# Sheet1.net
KiCad netlist of a schematic drawn in Altium Designer
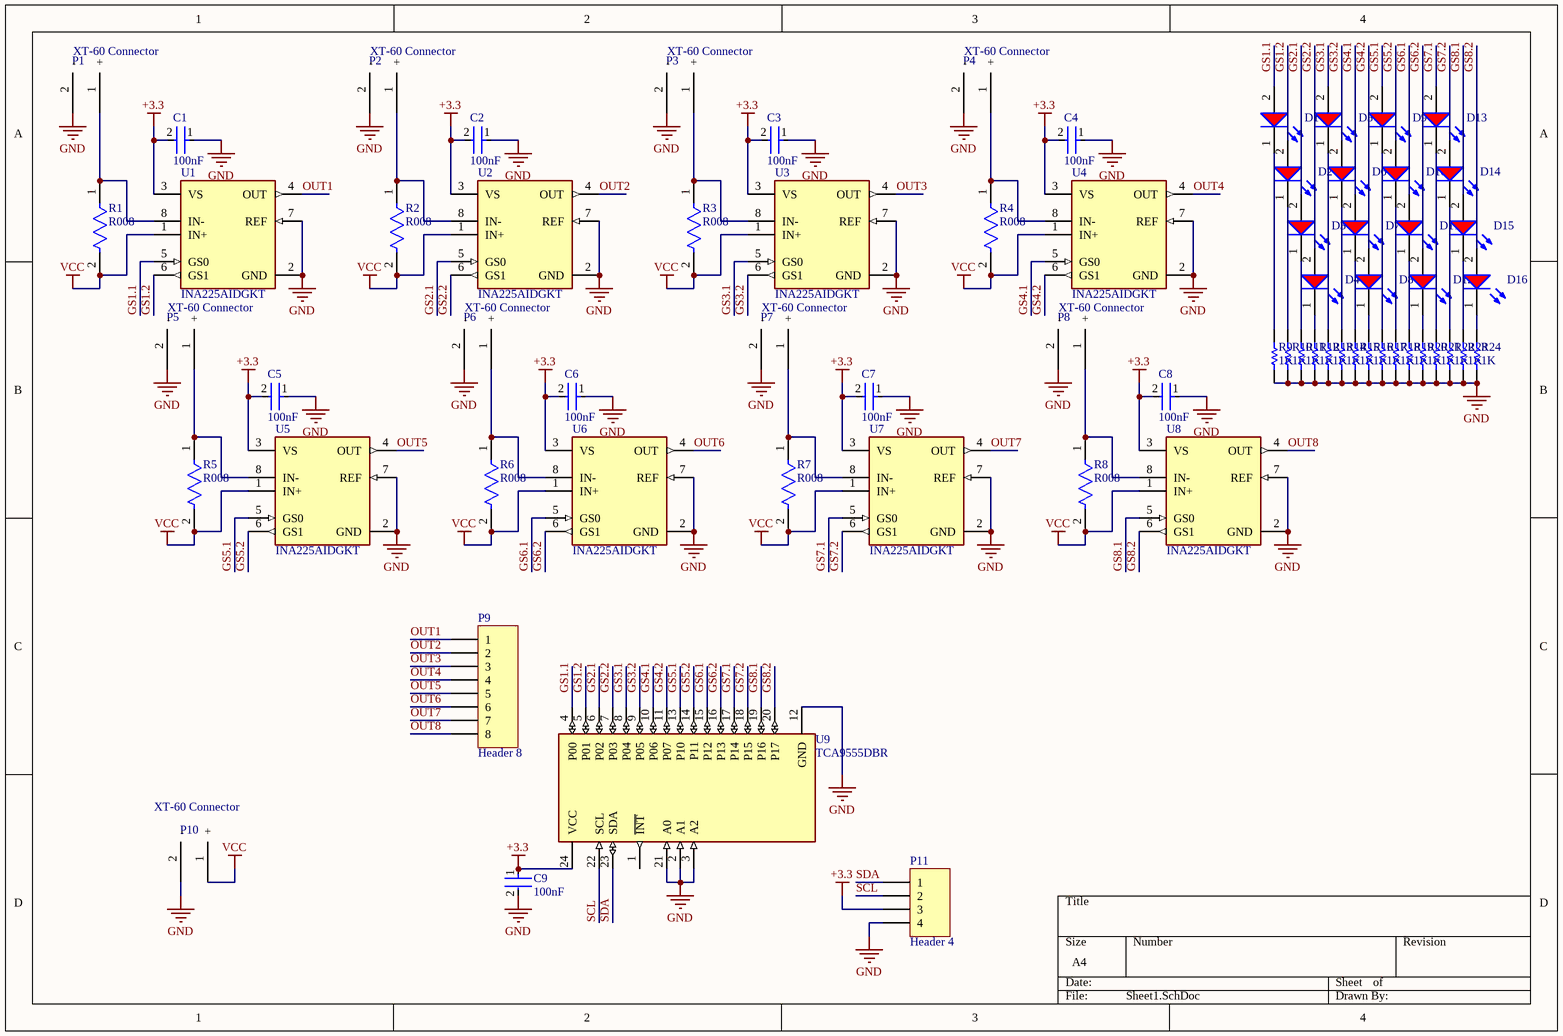
[diagram p0: Sheet1.SchDoc]

(export (version "E")
  (design (tool "Eeschema 10.0.6"))
  (components
    (comp (ref "C1")
      (value "100nF")
      (footprint "FP-0805-L_2_01_0_2-W_1_25-IPC_B")
      (description "General Purpose Ceramic Capacitor, 0805, 100nF, 10%, X7R, 15%, 100V")
      (fields (field (name "VOLTAGE") "100V") (field (name "TOLERANCE") "10%"))
      (libsource (lib "Altium Content Vault") (part "b4654b650e69147ec39a6b967a45e02"))
    )
    (comp (ref "C2")
      (value "100nF")
      (footprint "FP-0805-L_2_01_0_2-W_1_25-IPC_B")
      (description "General Purpose Ceramic Capacitor, 0805, 100nF, 10%, X7R, 15%, 100V")
      (fields (field (name "VOLTAGE") "100V") (field (name "TOLERANCE") "10%"))
      (libsource (lib "Altium Content Vault") (part "b4654b650e69147ec39a6b967a45e02"))
    )
    (comp (ref "C3")
      (value "100nF")
      (footprint "FP-0805-L_2_01_0_2-W_1_25-IPC_B")
      (description "General Purpose Ceramic Capacitor, 0805, 100nF, 10%, X7R, 15%, 100V")
      (fields (field (name "VOLTAGE") "100V") (field (name "TOLERANCE") "10%"))
      (libsource (lib "Altium Content Vault") (part "b4654b650e69147ec39a6b967a45e02"))
    )
    (comp (ref "C4")
      (value "100nF")
      (footprint "FP-0805-L_2_01_0_2-W_1_25-IPC_B")
      (description "General Purpose Ceramic Capacitor, 0805, 100nF, 10%, X7R, 15%, 100V")
      (fields (field (name "VOLTAGE") "100V") (field (name "TOLERANCE") "10%"))
      (libsource (lib "Altium Content Vault") (part "b4654b650e69147ec39a6b967a45e02"))
    )
    (comp (ref "C5")
      (value "100nF")
      (footprint "FP-0805-L_2_01_0_2-W_1_25-IPC_B")
      (description "General Purpose Ceramic Capacitor, 0805, 100nF, 10%, X7R, 15%, 100V")
      (fields (field (name "VOLTAGE") "100V") (field (name "TOLERANCE") "10%"))
      (libsource (lib "Altium Content Vault") (part "b4654b650e69147ec39a6b967a45e02"))
    )
    (comp (ref "C6")
      (value "100nF")
      (footprint "FP-0805-L_2_01_0_2-W_1_25-IPC_B")
      (description "General Purpose Ceramic Capacitor, 0805, 100nF, 10%, X7R, 15%, 100V")
      (fields (field (name "VOLTAGE") "100V") (field (name "TOLERANCE") "10%"))
      (libsource (lib "Altium Content Vault") (part "b4654b650e69147ec39a6b967a45e02"))
    )
    (comp (ref "C7")
      (value "100nF")
      (footprint "FP-0805-L_2_01_0_2-W_1_25-IPC_B")
      (description "General Purpose Ceramic Capacitor, 0805, 100nF, 10%, X7R, 15%, 100V")
      (fields (field (name "VOLTAGE") "100V") (field (name "TOLERANCE") "10%"))
      (libsource (lib "Altium Content Vault") (part "b4654b650e69147ec39a6b967a45e02"))
    )
    (comp (ref "C8")
      (value "100nF")
      (footprint "FP-0805-L_2_01_0_2-W_1_25-IPC_B")
      (description "General Purpose Ceramic Capacitor, 0805, 100nF, 10%, X7R, 15%, 100V")
      (fields (field (name "VOLTAGE") "100V") (field (name "TOLERANCE") "10%"))
      (libsource (lib "Altium Content Vault") (part "b4654b650e69147ec39a6b967a45e02"))
    )
    (comp (ref "C9")
      (value "100nF")
      (footprint "FP-0805-L_2_01_0_2-W_1_25-IPC_B")
      (description "General Purpose Ceramic Capacitor, 0805, 100nF, 10%, X7R, 15%, 100V")
      (fields (field (name "VOLTAGE") "100V") (field (name "TOLERANCE") "10%"))
      (libsource (lib "Altium Content Vault") (part "b4654b650e69147ec39a6b967a45e02"))
    )
    (comp (ref "D1")
      (value "150080SS75000")
      (footprint "WL-SMCW_0805_150080xx75000")
      (libsource (lib "Altium Content Vault") (part "LED_Red_2A-1K"))
    )
    (comp (ref "D2")
      (value "150080SS75000")
      (footprint "WL-SMCW_0805_150080xx75000")
      (libsource (lib "Altium Content Vault") (part "LED_Red_2A-1K"))
    )
    (comp (ref "D3")
      (value "150080SS75000")
      (footprint "WL-SMCW_0805_150080xx75000")
      (libsource (lib "Altium Content Vault") (part "LED_Red_2A-1K"))
    )
    (comp (ref "D4")
      (value "150080SS75000")
      (footprint "WL-SMCW_0805_150080xx75000")
      (libsource (lib "Altium Content Vault") (part "LED_Red_2A-1K"))
    )
    (comp (ref "D5")
      (value "150080SS75000")
      (footprint "WL-SMCW_0805_150080xx75000")
      (libsource (lib "Altium Content Vault") (part "LED_Red_2A-1K"))
    )
    (comp (ref "D6")
      (value "150080SS75000")
      (footprint "WL-SMCW_0805_150080xx75000")
      (libsource (lib "Altium Content Vault") (part "LED_Red_2A-1K"))
    )
    (comp (ref "D7")
      (value "150080SS75000")
      (footprint "WL-SMCW_0805_150080xx75000")
      (libsource (lib "Altium Content Vault") (part "LED_Red_2A-1K"))
    )
    (comp (ref "D8")
      (value "150080SS75000")
      (footprint "WL-SMCW_0805_150080xx75000")
      (libsource (lib "Altium Content Vault") (part "LED_Red_2A-1K"))
    )
    (comp (ref "D9")
      (value "150080SS75000")
      (footprint "WL-SMCW_0805_150080xx75000")
      (libsource (lib "Altium Content Vault") (part "LED_Red_2A-1K"))
    )
    (comp (ref "D10")
      (value "150080SS75000")
      (footprint "WL-SMCW_0805_150080xx75000")
      (libsource (lib "Altium Content Vault") (part "LED_Red_2A-1K"))
    )
    (comp (ref "D11")
      (value "150080SS75000")
      (footprint "WL-SMCW_0805_150080xx75000")
      (libsource (lib "Altium Content Vault") (part "LED_Red_2A-1K"))
    )
    (comp (ref "D12")
      (value "150080SS75000")
      (footprint "WL-SMCW_0805_150080xx75000")
      (libsource (lib "Altium Content Vault") (part "LED_Red_2A-1K"))
    )
    (comp (ref "D13")
      (value "150080SS75000")
      (footprint "WL-SMCW_0805_150080xx75000")
      (libsource (lib "Altium Content Vault") (part "LED_Red_2A-1K"))
    )
    (comp (ref "D14")
      (value "150080SS75000")
      (footprint "WL-SMCW_0805_150080xx75000")
      (libsource (lib "Altium Content Vault") (part "LED_Red_2A-1K"))
    )
    (comp (ref "D15")
      (value "150080SS75000")
      (footprint "WL-SMCW_0805_150080xx75000")
      (libsource (lib "Altium Content Vault") (part "LED_Red_2A-1K"))
    )
    (comp (ref "D16")
      (value "150080SS75000")
      (footprint "WL-SMCW_0805_150080xx75000")
      (libsource (lib "Altium Content Vault") (part "LED_Red_2A-1K"))
    )
    (comp (ref "P1")
      (value "XT-60 Connector")
      (footprint "2")
      (fields
        (field (name "MANUFACTURER") "POLOLU")
        (field (name "MANUFACTURER PART NUMBER") "XT60 YELLOW")
        (field (name "SUPPLIER PART NUMBER 1") "XT-60 Connector")
      )
      (libsource (lib "AltiumLibraryDDT") (part "XT-60 Connector"))
    )
    (comp (ref "P2")
      (value "XT-60 Connector")
      (footprint "2")
      (fields
        (field (name "MANUFACTURER") "POLOLU")
        (field (name "MANUFACTURER PART NUMBER") "XT60 YELLOW")
        (field (name "SUPPLIER PART NUMBER 1") "XT-60 Connector")
      )
      (libsource (lib "AltiumLibraryDDT") (part "XT-60 Connector"))
    )
    (comp (ref "P3")
      (value "XT-60 Connector")
      (footprint "2")
      (fields
        (field (name "MANUFACTURER") "POLOLU")
        (field (name "MANUFACTURER PART NUMBER") "XT60 YELLOW")
        (field (name "SUPPLIER PART NUMBER 1") "XT-60 Connector")
      )
      (libsource (lib "AltiumLibraryDDT") (part "XT-60 Connector"))
    )
    (comp (ref "P4")
      (value "XT-60 Connector")
      (footprint "2")
      (fields
        (field (name "MANUFACTURER") "POLOLU")
        (field (name "MANUFACTURER PART NUMBER") "XT60 YELLOW")
        (field (name "SUPPLIER PART NUMBER 1") "XT-60 Connector")
      )
      (libsource (lib "AltiumLibraryDDT") (part "XT-60 Connector"))
    )
    (comp (ref "P5")
      (value "XT-60 Connector")
      (footprint "2")
      (fields
        (field (name "MANUFACTURER") "POLOLU")
        (field (name "MANUFACTURER PART NUMBER") "XT60 YELLOW")
        (field (name "SUPPLIER PART NUMBER 1") "XT-60 Connector")
      )
      (libsource (lib "AltiumLibraryDDT") (part "XT-60 Connector"))
    )
    (comp (ref "P6")
      (value "XT-60 Connector")
      (footprint "2")
      (fields
        (field (name "MANUFACTURER") "POLOLU")
        (field (name "MANUFACTURER PART NUMBER") "XT60 YELLOW")
        (field (name "SUPPLIER PART NUMBER 1") "XT-60 Connector")
      )
      (libsource (lib "AltiumLibraryDDT") (part "XT-60 Connector"))
    )
    (comp (ref "P7")
      (value "XT-60 Connector")
      (footprint "2")
      (fields
        (field (name "MANUFACTURER") "POLOLU")
        (field (name "MANUFACTURER PART NUMBER") "XT60 YELLOW")
        (field (name "SUPPLIER PART NUMBER 1") "XT-60 Connector")
      )
      (libsource (lib "AltiumLibraryDDT") (part "XT-60 Connector"))
    )
    (comp (ref "P8")
      (value "XT-60 Connector")
      (footprint "2")
      (fields
        (field (name "MANUFACTURER") "POLOLU")
        (field (name "MANUFACTURER PART NUMBER") "XT60 YELLOW")
        (field (name "SUPPLIER PART NUMBER 1") "XT-60 Connector")
      )
      (libsource (lib "AltiumLibraryDDT") (part "XT-60 Connector"))
    )
    (comp (ref "P9")
      (value "Header 8")
      (footprint "HDR1X8")
      (description "Header, 8-Pin")
      (fields (field (name "PUBLISHER") "Altium Limited"))
      (libsource (lib "Miscellaneous Connectors") (part "Header 8"))
    )
    (comp (ref "P10")
      (value "XT-60 Connector")
      (footprint "2")
      (fields
        (field (name "MANUFACTURER") "POLOLU")
        (field (name "MANUFACTURER PART NUMBER") "XT60 YELLOW")
        (field (name "SUPPLIER PART NUMBER 1") "XT-60 Connector")
      )
      (libsource (lib "AltiumLibraryDDT") (part "XT-60 Connector"))
    )
    (comp (ref "P11")
      (value "Header 4")
      (footprint "HDR1X4")
      (description "Header, 4-Pin")
      (fields (field (name "PUBLISHER") "Altium Limited"))
      (libsource (lib "Miscellaneous Connectors") (part "Header 4"))
    )
    (comp (ref "R1")
      (value "R008")
      (footprint "FP-RL2512-MFG")
      (description "RES 0.1 OHM 1% 1W 2512")
      (fields
        (field (name "OCTOPART") "https://octopart.com/rl2512fk-070r1l-yageo-42334369")
        (field (name "MANUFACTURER") "YAGEO")
      )
      (libsource (lib "Altium Content Vault") (part "1029c3af85768c4190bb7ad29bc67b5"))
    )
    (comp (ref "R2")
      (value "R008")
      (footprint "FP-RL2512-MFG")
      (description "RES 0.1 OHM 1% 1W 2512")
      (fields
        (field (name "OCTOPART") "https://octopart.com/rl2512fk-070r1l-yageo-42334369")
        (field (name "MANUFACTURER") "YAGEO")
      )
      (libsource (lib "Altium Content Vault") (part "1029c3af85768c4190bb7ad29bc67b5"))
    )
    (comp (ref "R3")
      (value "R008")
      (footprint "FP-RL2512-MFG")
      (description "RES 0.1 OHM 1% 1W 2512")
      (fields
        (field (name "OCTOPART") "https://octopart.com/rl2512fk-070r1l-yageo-42334369")
        (field (name "MANUFACTURER") "YAGEO")
      )
      (libsource (lib "Altium Content Vault") (part "1029c3af85768c4190bb7ad29bc67b5"))
    )
    (comp (ref "R4")
      (value "R008")
      (footprint "FP-RL2512-MFG")
      (description "RES 0.1 OHM 1% 1W 2512")
      (fields
        (field (name "OCTOPART") "https://octopart.com/rl2512fk-070r1l-yageo-42334369")
        (field (name "MANUFACTURER") "YAGEO")
      )
      (libsource (lib "Altium Content Vault") (part "1029c3af85768c4190bb7ad29bc67b5"))
    )
    (comp (ref "R5")
      (value "R008")
      (footprint "FP-RL2512-MFG")
      (description "RES 0.1 OHM 1% 1W 2512")
      (fields
        (field (name "OCTOPART") "https://octopart.com/rl2512fk-070r1l-yageo-42334369")
        (field (name "MANUFACTURER") "YAGEO")
      )
      (libsource (lib "Altium Content Vault") (part "1029c3af85768c4190bb7ad29bc67b5"))
    )
    (comp (ref "R6")
      (value "R008")
      (footprint "FP-RL2512-MFG")
      (description "RES 0.1 OHM 1% 1W 2512")
      (fields
        (field (name "OCTOPART") "https://octopart.com/rl2512fk-070r1l-yageo-42334369")
        (field (name "MANUFACTURER") "YAGEO")
      )
      (libsource (lib "Altium Content Vault") (part "1029c3af85768c4190bb7ad29bc67b5"))
    )
    (comp (ref "R7")
      (value "R008")
      (footprint "FP-RL2512-MFG")
      (description "RES 0.1 OHM 1% 1W 2512")
      (fields
        (field (name "OCTOPART") "https://octopart.com/rl2512fk-070r1l-yageo-42334369")
        (field (name "MANUFACTURER") "YAGEO")
      )
      (libsource (lib "Altium Content Vault") (part "1029c3af85768c4190bb7ad29bc67b5"))
    )
    (comp (ref "R8")
      (value "R008")
      (footprint "FP-RL2512-MFG")
      (description "RES 0.1 OHM 1% 1W 2512")
      (fields
        (field (name "OCTOPART") "https://octopart.com/rl2512fk-070r1l-yageo-42334369")
        (field (name "MANUFACTURER") "YAGEO")
      )
      (libsource (lib "Altium Content Vault") (part "1029c3af85768c4190bb7ad29bc67b5"))
    )
    (comp (ref "R9")
      (value "1K")
      (footprint "RESC2013X60X35ML10T20")
      (description "Chip Resistor, 1 KOhm, +/- 1%, 125 mW, -55 to 155 degC, 0805 (2012 Metric), RoHS, Tape and Reel")
      (fields (field (name "TOLERANCE") "1%") (field (name "MANUFACTURER") "Yageo"))
      (libsource (lib "Altium Content Vault") (part "RES-2"))
    )
    (comp (ref "R10")
      (value "1K")
      (footprint "RESC2013X60X35ML10T20")
      (description "Chip Resistor, 1 KOhm, +/- 1%, 125 mW, -55 to 155 degC, 0805 (2012 Metric), RoHS, Tape and Reel")
      (fields (field (name "TOLERANCE") "1%") (field (name "MANUFACTURER") "Yageo"))
      (libsource (lib "Altium Content Vault") (part "RES-2"))
    )
    (comp (ref "R11")
      (value "1K")
      (footprint "RESC2013X60X35ML10T20")
      (description "Chip Resistor, 1 KOhm, +/- 1%, 125 mW, -55 to 155 degC, 0805 (2012 Metric), RoHS, Tape and Reel")
      (fields (field (name "TOLERANCE") "1%") (field (name "MANUFACTURER") "Yageo"))
      (libsource (lib "Altium Content Vault") (part "RES-2"))
    )
    (comp (ref "R12")
      (value "1K")
      (footprint "RESC2013X60X35ML10T20")
      (description "Chip Resistor, 1 KOhm, +/- 1%, 125 mW, -55 to 155 degC, 0805 (2012 Metric), RoHS, Tape and Reel")
      (fields (field (name "TOLERANCE") "1%") (field (name "MANUFACTURER") "Yageo"))
      (libsource (lib "Altium Content Vault") (part "RES-2"))
    )
    (comp (ref "R13")
      (value "1K")
      (footprint "RESC2013X60X35ML10T20")
      (description "Chip Resistor, 1 KOhm, +/- 1%, 125 mW, -55 to 155 degC, 0805 (2012 Metric), RoHS, Tape and Reel")
      (fields (field (name "TOLERANCE") "1%") (field (name "MANUFACTURER") "Yageo"))
      (libsource (lib "Altium Content Vault") (part "RES-2"))
    )
    (comp (ref "R14")
      (value "1K")
      (footprint "RESC2013X60X35ML10T20")
      (description "Chip Resistor, 1 KOhm, +/- 1%, 125 mW, -55 to 155 degC, 0805 (2012 Metric), RoHS, Tape and Reel")
      (fields (field (name "TOLERANCE") "1%") (field (name "MANUFACTURER") "Yageo"))
      (libsource (lib "Altium Content Vault") (part "RES-2"))
    )
    (comp (ref "R15")
      (value "1K")
      (footprint "RESC2013X60X35ML10T20")
      (description "Chip Resistor, 1 KOhm, +/- 1%, 125 mW, -55 to 155 degC, 0805 (2012 Metric), RoHS, Tape and Reel")
      (fields (field (name "TOLERANCE") "1%") (field (name "MANUFACTURER") "Yageo"))
      (libsource (lib "Altium Content Vault") (part "RES-2"))
    )
    (comp (ref "R16")
      (value "1K")
      (footprint "RESC2013X60X35ML10T20")
      (description "Chip Resistor, 1 KOhm, +/- 1%, 125 mW, -55 to 155 degC, 0805 (2012 Metric), RoHS, Tape and Reel")
      (fields (field (name "TOLERANCE") "1%") (field (name "MANUFACTURER") "Yageo"))
      (libsource (lib "Altium Content Vault") (part "RES-2"))
    )
    (comp (ref "R17")
      (value "1K")
      (footprint "RESC2013X60X35ML10T20")
      (description "Chip Resistor, 1 KOhm, +/- 1%, 125 mW, -55 to 155 degC, 0805 (2012 Metric), RoHS, Tape and Reel")
      (fields (field (name "TOLERANCE") "1%") (field (name "MANUFACTURER") "Yageo"))
      (libsource (lib "Altium Content Vault") (part "RES-2"))
    )
    (comp (ref "R18")
      (value "1K")
      (footprint "RESC2013X60X35ML10T20")
      (description "Chip Resistor, 1 KOhm, +/- 1%, 125 mW, -55 to 155 degC, 0805 (2012 Metric), RoHS, Tape and Reel")
      (fields (field (name "TOLERANCE") "1%") (field (name "MANUFACTURER") "Yageo"))
      (libsource (lib "Altium Content Vault") (part "RES-2"))
    )
    (comp (ref "R19")
      (value "1K")
      (footprint "RESC2013X60X35ML10T20")
      (description "Chip Resistor, 1 KOhm, +/- 1%, 125 mW, -55 to 155 degC, 0805 (2012 Metric), RoHS, Tape and Reel")
      (fields (field (name "TOLERANCE") "1%") (field (name "MANUFACTURER") "Yageo"))
      (libsource (lib "Altium Content Vault") (part "RES-2"))
    )
    (comp (ref "R20")
      (value "1K")
      (footprint "RESC2013X60X35ML10T20")
      (description "Chip Resistor, 1 KOhm, +/- 1%, 125 mW, -55 to 155 degC, 0805 (2012 Metric), RoHS, Tape and Reel")
      (fields (field (name "TOLERANCE") "1%") (field (name "MANUFACTURER") "Yageo"))
      (libsource (lib "Altium Content Vault") (part "RES-2"))
    )
    (comp (ref "R21")
      (value "1K")
      (footprint "RESC2013X60X35ML10T20")
      (description "Chip Resistor, 1 KOhm, +/- 1%, 125 mW, -55 to 155 degC, 0805 (2012 Metric), RoHS, Tape and Reel")
      (fields (field (name "TOLERANCE") "1%") (field (name "MANUFACTURER") "Yageo"))
      (libsource (lib "Altium Content Vault") (part "RES-2"))
    )
    (comp (ref "R22")
      (value "1K")
      (footprint "RESC2013X60X35ML10T20")
      (description "Chip Resistor, 1 KOhm, +/- 1%, 125 mW, -55 to 155 degC, 0805 (2012 Metric), RoHS, Tape and Reel")
      (fields (field (name "TOLERANCE") "1%") (field (name "MANUFACTURER") "Yageo"))
      (libsource (lib "Altium Content Vault") (part "RES-2"))
    )
    (comp (ref "R23")
      (value "1K")
      (footprint "RESC2013X60X35ML10T20")
      (description "Chip Resistor, 1 KOhm, +/- 1%, 125 mW, -55 to 155 degC, 0805 (2012 Metric), RoHS, Tape and Reel")
      (fields (field (name "TOLERANCE") "1%") (field (name "MANUFACTURER") "Yageo"))
      (libsource (lib "Altium Content Vault") (part "RES-2"))
    )
    (comp (ref "R24")
      (value "1K")
      (footprint "RESC2013X60X35ML10T20")
      (description "Chip Resistor, 1 KOhm, +/- 1%, 125 mW, -55 to 155 degC, 0805 (2012 Metric), RoHS, Tape and Reel")
      (fields (field (name "TOLERANCE") "1%") (field (name "MANUFACTURER") "Yageo"))
      (libsource (lib "Altium Content Vault") (part "RES-2"))
    )
    (comp (ref "U1")
      (value "INA225AIDGKT")
      (footprint "FP-INA225AIDGKT-IPC_A")
      (description "IC MONITOR PWR/CUR BIDIR 8VSSOP")
      (fields
        (field (name "OCTOPART") "https://octopart.com/ina225aidgkt-texas+instruments-28946314")
        (field (name "MANUFACTURER") "Texas Instruments")
      )
      (libsource (lib "Altium Content Vault") (part "c359911d667b8e4eb68c8ff16fe5c28"))
    )
    (comp (ref "U2")
      (value "INA225AIDGKT")
      (footprint "FP-INA225AIDGKT-IPC_A")
      (description "IC MONITOR PWR/CUR BIDIR 8VSSOP")
      (fields
        (field (name "OCTOPART") "https://octopart.com/ina225aidgkt-texas+instruments-28946314")
        (field (name "MANUFACTURER") "Texas Instruments")
      )
      (libsource (lib "Altium Content Vault") (part "c359911d667b8e4eb68c8ff16fe5c28"))
    )
    (comp (ref "U3")
      (value "INA225AIDGKT")
      (footprint "FP-INA225AIDGKT-IPC_A")
      (description "IC MONITOR PWR/CUR BIDIR 8VSSOP")
      (fields
        (field (name "OCTOPART") "https://octopart.com/ina225aidgkt-texas+instruments-28946314")
        (field (name "MANUFACTURER") "Texas Instruments")
      )
      (libsource (lib "Altium Content Vault") (part "c359911d667b8e4eb68c8ff16fe5c28"))
    )
    (comp (ref "U4")
      (value "INA225AIDGKT")
      (footprint "FP-INA225AIDGKT-IPC_A")
      (description "IC MONITOR PWR/CUR BIDIR 8VSSOP")
      (fields
        (field (name "OCTOPART") "https://octopart.com/ina225aidgkt-texas+instruments-28946314")
        (field (name "MANUFACTURER") "Texas Instruments")
      )
      (libsource (lib "Altium Content Vault") (part "c359911d667b8e4eb68c8ff16fe5c28"))
    )
    (comp (ref "U5")
      (value "INA225AIDGKT")
      (footprint "FP-INA225AIDGKT-IPC_A")
      (description "IC MONITOR PWR/CUR BIDIR 8VSSOP")
      (fields
        (field (name "OCTOPART") "https://octopart.com/ina225aidgkt-texas+instruments-28946314")
        (field (name "MANUFACTURER") "Texas Instruments")
      )
      (libsource (lib "Altium Content Vault") (part "c359911d667b8e4eb68c8ff16fe5c28"))
    )
    (comp (ref "U6")
      (value "INA225AIDGKT")
      (footprint "FP-INA225AIDGKT-IPC_A")
      (description "IC MONITOR PWR/CUR BIDIR 8VSSOP")
      (fields
        (field (name "OCTOPART") "https://octopart.com/ina225aidgkt-texas+instruments-28946314")
        (field (name "MANUFACTURER") "Texas Instruments")
      )
      (libsource (lib "Altium Content Vault") (part "c359911d667b8e4eb68c8ff16fe5c28"))
    )
    (comp (ref "U7")
      (value "INA225AIDGKT")
      (footprint "FP-INA225AIDGKT-IPC_A")
      (description "IC MONITOR PWR/CUR BIDIR 8VSSOP")
      (fields
        (field (name "OCTOPART") "https://octopart.com/ina225aidgkt-texas+instruments-28946314")
        (field (name "MANUFACTURER") "Texas Instruments")
      )
      (libsource (lib "Altium Content Vault") (part "c359911d667b8e4eb68c8ff16fe5c28"))
    )
    (comp (ref "U8")
      (value "INA225AIDGKT")
      (footprint "FP-INA225AIDGKT-IPC_A")
      (description "IC MONITOR PWR/CUR BIDIR 8VSSOP")
      (fields
        (field (name "OCTOPART") "https://octopart.com/ina225aidgkt-texas+instruments-28946314")
        (field (name "MANUFACTURER") "Texas Instruments")
      )
      (libsource (lib "Altium Content Vault") (part "c359911d667b8e4eb68c8ff16fe5c28"))
    )
    (comp (ref "U9")
      (value "TCA9555DBR")
      (footprint "FP-DB0024A-IPC_A")
      (description "IC I/O EXPANDER 16B 24SSOP")
      (libsource (lib "Altium Content Vault") (part "d0eb17f36d141fc89679fdc1217173a"))
    )
  )
  (nets
    (net (code "1") (name "+3.3") (class "Default")
      (node (ref "C1") (pin "2") (pinfunction "2_2") (pintype "passive"))
      (node (ref "C2") (pin "2") (pinfunction "2_2") (pintype "passive"))
      (node (ref "C3") (pin "2") (pinfunction "2_2") (pintype "passive"))
      (node (ref "C4") (pin "2") (pinfunction "2_2") (pintype "passive"))
      (node (ref "C5") (pin "2") (pinfunction "2_2") (pintype "passive"))
      (node (ref "C6") (pin "2") (pinfunction "2_2") (pintype "passive"))
      (node (ref "C7") (pin "2") (pinfunction "2_2") (pintype "passive"))
      (node (ref "C8") (pin "2") (pinfunction "2_2") (pintype "passive"))
      (node (ref "C9") (pin "1") (pinfunction "1_1") (pintype "passive"))
      (node (ref "P11") (pin "3") (pinfunction "3_3") (pintype "passive"))
      (node (ref "U1") (pin "3") (pinfunction "VS_3") (pintype "power_in"))
      (node (ref "U2") (pin "3") (pinfunction "VS_3") (pintype "power_in"))
      (node (ref "U3") (pin "3") (pinfunction "VS_3") (pintype "power_in"))
      (node (ref "U4") (pin "3") (pinfunction "VS_3") (pintype "power_in"))
      (node (ref "U5") (pin "3") (pinfunction "VS_3") (pintype "power_in"))
      (node (ref "U6") (pin "3") (pinfunction "VS_3") (pintype "power_in"))
      (node (ref "U7") (pin "3") (pinfunction "VS_3") (pintype "power_in"))
      (node (ref "U8") (pin "3") (pinfunction "VS_3") (pintype "power_in"))
      (node (ref "U9") (pin "24") (pinfunction "VCC_24") (pintype "power_in"))
    )
    (net (code "2") (name "/GS1.1") (class "Default")
      (node (ref "D1") (pin "2") (pinfunction "A_2") (pintype "passive"))
      (node (ref "U1") (pin "5") (pinfunction "GS0_5") (pintype "input"))
      (node (ref "U9") (pin "4") (pinfunction "P00_4") (pintype "bidirectional"))
    )
    (net (code "3") (name "/GS1.2") (class "Default")
      (node (ref "D2") (pin "2") (pinfunction "A_2") (pintype "passive"))
      (node (ref "U1") (pin "6") (pinfunction "GS1_6") (pintype "output"))
      (node (ref "U9") (pin "5") (pinfunction "P01_5") (pintype "bidirectional"))
    )
    (net (code "4") (name "/GS2.1") (class "Default")
      (node (ref "D3") (pin "2") (pinfunction "A_2") (pintype "passive"))
      (node (ref "U2") (pin "5") (pinfunction "GS0_5") (pintype "input"))
      (node (ref "U9") (pin "6") (pinfunction "P02_6") (pintype "bidirectional"))
    )
    (net (code "5") (name "/GS2.2") (class "Default")
      (node (ref "D4") (pin "2") (pinfunction "A_2") (pintype "passive"))
      (node (ref "U2") (pin "6") (pinfunction "GS1_6") (pintype "output"))
      (node (ref "U9") (pin "7") (pinfunction "P03_7") (pintype "bidirectional"))
    )
    (net (code "6") (name "/GS3.1") (class "Default")
      (node (ref "D5") (pin "2") (pinfunction "A_2") (pintype "passive"))
      (node (ref "U3") (pin "5") (pinfunction "GS0_5") (pintype "input"))
      (node (ref "U9") (pin "8") (pinfunction "P04_8") (pintype "bidirectional"))
    )
    (net (code "7") (name "/GS3.2") (class "Default")
      (node (ref "D6") (pin "2") (pinfunction "A_2") (pintype "passive"))
      (node (ref "U3") (pin "6") (pinfunction "GS1_6") (pintype "output"))
      (node (ref "U9") (pin "9") (pinfunction "P05_9") (pintype "bidirectional"))
    )
    (net (code "8") (name "/GS4.1") (class "Default")
      (node (ref "D7") (pin "2") (pinfunction "A_2") (pintype "passive"))
      (node (ref "U4") (pin "5") (pinfunction "GS0_5") (pintype "input"))
      (node (ref "U9") (pin "10") (pinfunction "P06_10") (pintype "bidirectional"))
    )
    (net (code "9") (name "/GS4.2") (class "Default")
      (node (ref "D8") (pin "2") (pinfunction "A_2") (pintype "passive"))
      (node (ref "U4") (pin "6") (pinfunction "GS1_6") (pintype "output"))
      (node (ref "U9") (pin "11") (pinfunction "P07_11") (pintype "bidirectional"))
    )
    (net (code "10") (name "/GS5.1") (class "Default")
      (node (ref "D9") (pin "2") (pinfunction "A_2") (pintype "passive"))
      (node (ref "U5") (pin "5") (pinfunction "GS0_5") (pintype "input"))
      (node (ref "U9") (pin "13") (pinfunction "P10_13") (pintype "bidirectional"))
    )
    (net (code "11") (name "/GS5.2") (class "Default")
      (node (ref "D10") (pin "2") (pinfunction "A_2") (pintype "passive"))
      (node (ref "U5") (pin "6") (pinfunction "GS1_6") (pintype "output"))
      (node (ref "U9") (pin "14") (pinfunction "P11_14") (pintype "bidirectional"))
    )
    (net (code "12") (name "/GS6.1") (class "Default")
      (node (ref "D11") (pin "2") (pinfunction "A_2") (pintype "passive"))
      (node (ref "U6") (pin "5") (pinfunction "GS0_5") (pintype "input"))
      (node (ref "U9") (pin "15") (pinfunction "P12_15") (pintype "bidirectional"))
    )
    (net (code "13") (name "/GS6.2") (class "Default")
      (node (ref "D12") (pin "2") (pinfunction "A_2") (pintype "passive"))
      (node (ref "U6") (pin "6") (pinfunction "GS1_6") (pintype "output"))
      (node (ref "U9") (pin "16") (pinfunction "P13_16") (pintype "bidirectional"))
    )
    (net (code "14") (name "/GS7.1") (class "Default")
      (node (ref "D13") (pin "2") (pinfunction "A_2") (pintype "passive"))
      (node (ref "U7") (pin "5") (pinfunction "GS0_5") (pintype "input"))
      (node (ref "U9") (pin "17") (pinfunction "P14_17") (pintype "bidirectional"))
    )
    (net (code "15") (name "/GS7.2") (class "Default")
      (node (ref "D14") (pin "2") (pinfunction "A_2") (pintype "passive"))
      (node (ref "U7") (pin "6") (pinfunction "GS1_6") (pintype "output"))
      (node (ref "U9") (pin "18") (pinfunction "P15_18") (pintype "bidirectional"))
    )
    (net (code "16") (name "/GS8.1") (class "Default")
      (node (ref "D15") (pin "2") (pinfunction "A_2") (pintype "passive"))
      (node (ref "U8") (pin "5") (pinfunction "GS0_5") (pintype "input"))
      (node (ref "U9") (pin "19") (pinfunction "P16_19") (pintype "bidirectional"))
    )
    (net (code "17") (name "/GS8.2") (class "Default")
      (node (ref "D16") (pin "2") (pinfunction "A_2") (pintype "passive"))
      (node (ref "U8") (pin "6") (pinfunction "GS1_6") (pintype "output"))
      (node (ref "U9") (pin "20") (pinfunction "P17_20") (pintype "bidirectional"))
    )
    (net (code "18") (name "/OUT1") (class "Default")
      (node (ref "P9") (pin "1") (pinfunction "1_1") (pintype "passive"))
      (node (ref "U1") (pin "4") (pinfunction "OUT_4") (pintype "output"))
    )
    (net (code "19") (name "/OUT2") (class "Default")
      (node (ref "P9") (pin "2") (pinfunction "2_2") (pintype "passive"))
      (node (ref "U2") (pin "4") (pinfunction "OUT_4") (pintype "output"))
    )
    (net (code "20") (name "/OUT3") (class "Default")
      (node (ref "P9") (pin "3") (pinfunction "3_3") (pintype "passive"))
      (node (ref "U3") (pin "4") (pinfunction "OUT_4") (pintype "output"))
    )
    (net (code "21") (name "/OUT4") (class "Default")
      (node (ref "P9") (pin "4") (pinfunction "4_4") (pintype "passive"))
      (node (ref "U4") (pin "4") (pinfunction "OUT_4") (pintype "output"))
    )
    (net (code "22") (name "/OUT5") (class "Default")
      (node (ref "P9") (pin "5") (pinfunction "5_5") (pintype "passive"))
      (node (ref "U5") (pin "4") (pinfunction "OUT_4") (pintype "output"))
    )
    (net (code "23") (name "/OUT6") (class "Default")
      (node (ref "P9") (pin "6") (pinfunction "6_6") (pintype "passive"))
      (node (ref "U6") (pin "4") (pinfunction "OUT_4") (pintype "output"))
    )
    (net (code "24") (name "/OUT7") (class "Default")
      (node (ref "P9") (pin "7") (pinfunction "7_7") (pintype "passive"))
      (node (ref "U7") (pin "4") (pinfunction "OUT_4") (pintype "output"))
    )
    (net (code "25") (name "/OUT8") (class "Default")
      (node (ref "P9") (pin "8") (pinfunction "8_8") (pintype "passive"))
      (node (ref "U8") (pin "4") (pinfunction "OUT_4") (pintype "output"))
    )
    (net (code "26") (name "/SCL") (class "Default")
      (node (ref "P11") (pin "2") (pinfunction "2_2") (pintype "passive"))
      (node (ref "U9") (pin "22") (pinfunction "SCL_22") (pintype "input"))
    )
    (net (code "27") (name "/SDA") (class "Default")
      (node (ref "P11") (pin "1") (pinfunction "1_1") (pintype "passive"))
      (node (ref "U9") (pin "23") (pinfunction "SDA_23") (pintype "bidirectional"))
    )
    (net (code "28") (name "GND") (class "Default")
      (node (ref "C1") (pin "1") (pinfunction "1_1") (pintype "passive"))
      (node (ref "C2") (pin "1") (pinfunction "1_1") (pintype "passive"))
      (node (ref "C3") (pin "1") (pinfunction "1_1") (pintype "passive"))
      (node (ref "C4") (pin "1") (pinfunction "1_1") (pintype "passive"))
      (node (ref "C5") (pin "1") (pinfunction "1_1") (pintype "passive"))
      (node (ref "C6") (pin "1") (pinfunction "1_1") (pintype "passive"))
      (node (ref "C7") (pin "1") (pinfunction "1_1") (pintype "passive"))
      (node (ref "C8") (pin "1") (pinfunction "1_1") (pintype "passive"))
      (node (ref "C9") (pin "2") (pinfunction "2_2") (pintype "passive"))
      (node (ref "P1") (pin "2") (pinfunction "-_2") (pintype "power_in"))
      (node (ref "P10") (pin "2") (pinfunction "-_2") (pintype "power_in"))
      (node (ref "P11") (pin "4") (pinfunction "4_4") (pintype "passive"))
      (node (ref "P2") (pin "2") (pinfunction "-_2") (pintype "power_in"))
      (node (ref "P3") (pin "2") (pinfunction "-_2") (pintype "power_in"))
      (node (ref "P4") (pin "2") (pinfunction "-_2") (pintype "power_in"))
      (node (ref "P5") (pin "2") (pinfunction "-_2") (pintype "power_in"))
      (node (ref "P6") (pin "2") (pinfunction "-_2") (pintype "power_in"))
      (node (ref "P7") (pin "2") (pinfunction "-_2") (pintype "power_in"))
      (node (ref "P8") (pin "2") (pinfunction "-_2") (pintype "power_in"))
      (node (ref "R10") (pin "1") (pinfunction "1_1") (pintype "passive"))
      (node (ref "R11") (pin "1") (pinfunction "1_1") (pintype "passive"))
      (node (ref "R12") (pin "1") (pinfunction "1_1") (pintype "passive"))
      (node (ref "R13") (pin "1") (pinfunction "1_1") (pintype "passive"))
      (node (ref "R14") (pin "1") (pinfunction "1_1") (pintype "passive"))
      (node (ref "R15") (pin "1") (pinfunction "1_1") (pintype "passive"))
      (node (ref "R16") (pin "1") (pinfunction "1_1") (pintype "passive"))
      (node (ref "R17") (pin "1") (pinfunction "1_1") (pintype "passive"))
      (node (ref "R18") (pin "1") (pinfunction "1_1") (pintype "passive"))
      (node (ref "R19") (pin "1") (pinfunction "1_1") (pintype "passive"))
      (node (ref "R20") (pin "1") (pinfunction "1_1") (pintype "passive"))
      (node (ref "R21") (pin "1") (pinfunction "1_1") (pintype "passive"))
      (node (ref "R22") (pin "1") (pinfunction "1_1") (pintype "passive"))
      (node (ref "R23") (pin "1") (pinfunction "1_1") (pintype "passive"))
      (node (ref "R24") (pin "1") (pinfunction "1_1") (pintype "passive"))
      (node (ref "R9") (pin "1") (pinfunction "1_1") (pintype "passive"))
      (node (ref "U1") (pin "2") (pinfunction "GND_2") (pintype "power_in"))
      (node (ref "U1") (pin "7") (pinfunction "REF_7") (pintype "input"))
      (node (ref "U2") (pin "2") (pinfunction "GND_2") (pintype "power_in"))
      (node (ref "U2") (pin "7") (pinfunction "REF_7") (pintype "input"))
      (node (ref "U3") (pin "2") (pinfunction "GND_2") (pintype "power_in"))
      (node (ref "U3") (pin "7") (pinfunction "REF_7") (pintype "input"))
      (node (ref "U4") (pin "2") (pinfunction "GND_2") (pintype "power_in"))
      (node (ref "U4") (pin "7") (pinfunction "REF_7") (pintype "input"))
      (node (ref "U5") (pin "2") (pinfunction "GND_2") (pintype "power_in"))
      (node (ref "U5") (pin "7") (pinfunction "REF_7") (pintype "input"))
      (node (ref "U6") (pin "2") (pinfunction "GND_2") (pintype "power_in"))
      (node (ref "U6") (pin "7") (pinfunction "REF_7") (pintype "input"))
      (node (ref "U7") (pin "2") (pinfunction "GND_2") (pintype "power_in"))
      (node (ref "U7") (pin "7") (pinfunction "REF_7") (pintype "input"))
      (node (ref "U8") (pin "2") (pinfunction "GND_2") (pintype "power_in"))
      (node (ref "U8") (pin "7") (pinfunction "REF_7") (pintype "input"))
      (node (ref "U9") (pin "12") (pinfunction "GND_12") (pintype "power_in"))
      (node (ref "U9") (pin "2") (pinfunction "A1_2") (pintype "input"))
      (node (ref "U9") (pin "21") (pinfunction "A0_21") (pintype "input"))
      (node (ref "U9") (pin "3") (pinfunction "A2_3") (pintype "input"))
    )
    (net (code "29") (name "Net-(D1-K)") (class "Default")
      (node (ref "D1") (pin "1") (pinfunction "K_1") (pintype "passive"))
      (node (ref "R9") (pin "2") (pinfunction "2_2") (pintype "passive"))
    )
    (net (code "30") (name "Net-(D2-K)") (class "Default")
      (node (ref "D2") (pin "1") (pinfunction "K_1") (pintype "passive"))
      (node (ref "R10") (pin "2") (pinfunction "2_2") (pintype "passive"))
    )
    (net (code "31") (name "Net-(D3-K)") (class "Default")
      (node (ref "D3") (pin "1") (pinfunction "K_1") (pintype "passive"))
      (node (ref "R11") (pin "2") (pinfunction "2_2") (pintype "passive"))
    )
    (net (code "32") (name "Net-(D4-K)") (class "Default")
      (node (ref "D4") (pin "1") (pinfunction "K_1") (pintype "passive"))
      (node (ref "R12") (pin "2") (pinfunction "2_2") (pintype "passive"))
    )
    (net (code "33") (name "Net-(D5-K)") (class "Default")
      (node (ref "D5") (pin "1") (pinfunction "K_1") (pintype "passive"))
      (node (ref "R13") (pin "2") (pinfunction "2_2") (pintype "passive"))
    )
    (net (code "34") (name "Net-(D6-K)") (class "Default")
      (node (ref "D6") (pin "1") (pinfunction "K_1") (pintype "passive"))
      (node (ref "R14") (pin "2") (pinfunction "2_2") (pintype "passive"))
    )
    (net (code "35") (name "Net-(D7-K)") (class "Default")
      (node (ref "D7") (pin "1") (pinfunction "K_1") (pintype "passive"))
      (node (ref "R15") (pin "2") (pinfunction "2_2") (pintype "passive"))
    )
    (net (code "36") (name "Net-(D8-K)") (class "Default")
      (node (ref "D8") (pin "1") (pinfunction "K_1") (pintype "passive"))
      (node (ref "R16") (pin "2") (pinfunction "2_2") (pintype "passive"))
    )
    (net (code "37") (name "Net-(D9-K)") (class "Default")
      (node (ref "D9") (pin "1") (pinfunction "K_1") (pintype "passive"))
      (node (ref "R17") (pin "2") (pinfunction "2_2") (pintype "passive"))
    )
    (net (code "38") (name "Net-(D10-K)") (class "Default")
      (node (ref "D10") (pin "1") (pinfunction "K_1") (pintype "passive"))
      (node (ref "R18") (pin "2") (pinfunction "2_2") (pintype "passive"))
    )
    (net (code "39") (name "Net-(D11-K)") (class "Default")
      (node (ref "D11") (pin "1") (pinfunction "K_1") (pintype "passive"))
      (node (ref "R19") (pin "2") (pinfunction "2_2") (pintype "passive"))
    )
    (net (code "40") (name "Net-(D12-K)") (class "Default")
      (node (ref "D12") (pin "1") (pinfunction "K_1") (pintype "passive"))
      (node (ref "R20") (pin "2") (pinfunction "2_2") (pintype "passive"))
    )
    (net (code "41") (name "Net-(D13-K)") (class "Default")
      (node (ref "D13") (pin "1") (pinfunction "K_1") (pintype "passive"))
      (node (ref "R21") (pin "2") (pinfunction "2_2") (pintype "passive"))
    )
    (net (code "42") (name "Net-(D14-K)") (class "Default")
      (node (ref "D14") (pin "1") (pinfunction "K_1") (pintype "passive"))
      (node (ref "R22") (pin "2") (pinfunction "2_2") (pintype "passive"))
    )
    (net (code "43") (name "Net-(D15-K)") (class "Default")
      (node (ref "D15") (pin "1") (pinfunction "K_1") (pintype "passive"))
      (node (ref "R23") (pin "2") (pinfunction "2_2") (pintype "passive"))
    )
    (net (code "44") (name "Net-(D16-K)") (class "Default")
      (node (ref "D16") (pin "1") (pinfunction "K_1") (pintype "passive"))
      (node (ref "R24") (pin "2") (pinfunction "2_2") (pintype "passive"))
    )
    (net (code "45") (name "Net-(P1-+)") (class "Default")
      (node (ref "P1") (pin "1") (pinfunction "+_1") (pintype "power_in"))
      (node (ref "R1") (pin "1") (pinfunction "1_1") (pintype "passive"))
      (node (ref "U1") (pin "8") (pinfunction "IN-_8") (pintype "tri_state"))
    )
    (net (code "46") (name "Net-(P2-+)") (class "Default")
      (node (ref "P2") (pin "1") (pinfunction "+_1") (pintype "power_in"))
      (node (ref "R2") (pin "1") (pinfunction "1_1") (pintype "passive"))
      (node (ref "U2") (pin "8") (pinfunction "IN-_8") (pintype "tri_state"))
    )
    (net (code "47") (name "Net-(P3-+)") (class "Default")
      (node (ref "P3") (pin "1") (pinfunction "+_1") (pintype "power_in"))
      (node (ref "R3") (pin "1") (pinfunction "1_1") (pintype "passive"))
      (node (ref "U3") (pin "8") (pinfunction "IN-_8") (pintype "tri_state"))
    )
    (net (code "48") (name "Net-(P4-+)") (class "Default")
      (node (ref "P4") (pin "1") (pinfunction "+_1") (pintype "power_in"))
      (node (ref "R4") (pin "1") (pinfunction "1_1") (pintype "passive"))
      (node (ref "U4") (pin "8") (pinfunction "IN-_8") (pintype "tri_state"))
    )
    (net (code "49") (name "Net-(P5-+)") (class "Default")
      (node (ref "P5") (pin "1") (pinfunction "+_1") (pintype "power_in"))
      (node (ref "R5") (pin "1") (pinfunction "1_1") (pintype "passive"))
      (node (ref "U5") (pin "8") (pinfunction "IN-_8") (pintype "tri_state"))
    )
    (net (code "50") (name "Net-(P6-+)") (class "Default")
      (node (ref "P6") (pin "1") (pinfunction "+_1") (pintype "power_in"))
      (node (ref "R6") (pin "1") (pinfunction "1_1") (pintype "passive"))
      (node (ref "U6") (pin "8") (pinfunction "IN-_8") (pintype "tri_state"))
    )
    (net (code "51") (name "Net-(P7-+)") (class "Default")
      (node (ref "P7") (pin "1") (pinfunction "+_1") (pintype "power_in"))
      (node (ref "R7") (pin "1") (pinfunction "1_1") (pintype "passive"))
      (node (ref "U7") (pin "8") (pinfunction "IN-_8") (pintype "tri_state"))
    )
    (net (code "52") (name "Net-(P8-+)") (class "Default")
      (node (ref "P8") (pin "1") (pinfunction "+_1") (pintype "power_in"))
      (node (ref "R8") (pin "1") (pinfunction "1_1") (pintype "passive"))
      (node (ref "U8") (pin "8") (pinfunction "IN-_8") (pintype "tri_state"))
    )
    (net (code "53") (name "VCC") (class "Default")
      (node (ref "P10") (pin "1") (pinfunction "+_1") (pintype "power_in"))
      (node (ref "R1") (pin "2") (pinfunction "2_2") (pintype "passive"))
      (node (ref "R2") (pin "2") (pinfunction "2_2") (pintype "passive"))
      (node (ref "R3") (pin "2") (pinfunction "2_2") (pintype "passive"))
      (node (ref "R4") (pin "2") (pinfunction "2_2") (pintype "passive"))
      (node (ref "R5") (pin "2") (pinfunction "2_2") (pintype "passive"))
      (node (ref "R6") (pin "2") (pinfunction "2_2") (pintype "passive"))
      (node (ref "R7") (pin "2") (pinfunction "2_2") (pintype "passive"))
      (node (ref "R8") (pin "2") (pinfunction "2_2") (pintype "passive"))
      (node (ref "U1") (pin "1") (pinfunction "IN+_1") (pintype "tri_state"))
      (node (ref "U2") (pin "1") (pinfunction "IN+_1") (pintype "tri_state"))
      (node (ref "U3") (pin "1") (pinfunction "IN+_1") (pintype "tri_state"))
      (node (ref "U4") (pin "1") (pinfunction "IN+_1") (pintype "tri_state"))
      (node (ref "U5") (pin "1") (pinfunction "IN+_1") (pintype "tri_state"))
      (node (ref "U6") (pin "1") (pinfunction "IN+_1") (pintype "tri_state"))
      (node (ref "U7") (pin "1") (pinfunction "IN+_1") (pintype "tri_state"))
      (node (ref "U8") (pin "1") (pinfunction "IN+_1") (pintype "tri_state"))
    )
    (net (code "54") (name "unconnected-(U9-~{INT}-Pad1)") (class "Default")
      (node (ref "U9") (pin "1") (pinfunction "~{INT}_1") (pintype "output"))
    )
  )
)
